# test_2.net
KiCad netlist of a schematic drawn in EAGLE
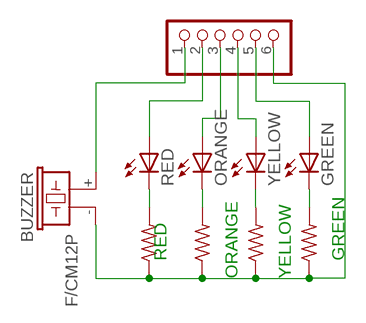
[diagram p0: schematic, sheet 1]

(export (version "E")
  (design (tool "Eeschema 10.0.6"))
  (components
    (comp (ref "BUZZER")
      (value "F/CM12P")
      (footprint "eagle-import:F_CM12P")
      (libsource (lib "eagle-import") (part "F/CM12P"))
    )
    (comp (ref "GND")
      (value "PINHD-1X6")
      (footprint "eagle-import:1X06")
      (libsource (lib "eagle-import") (part "PINHD-1X6"))
    )
    (comp (ref "GREEN")
      (value "LED5MM")
      (footprint "eagle-import:LED5MM")
      (libsource (lib "eagle-import") (part "LED5MM"))
    )
    (comp (ref "ORANGE")
      (value "LED5MM")
      (footprint "eagle-import:LED5MM")
      (libsource (lib "eagle-import") (part "LED5MM"))
    )
    (comp (ref "R1")
      (value "R-US_0204/7")
      (footprint "eagle-import:0204_7")
      (libsource (lib "eagle-import") (part "R-US_0204/7"))
    )
    (comp (ref "R2")
      (value "R-US_0204/7")
      (footprint "eagle-import:0204_7")
      (libsource (lib "eagle-import") (part "R-US_0204/7"))
    )
    (comp (ref "R3")
      (value "R-US_0204/7")
      (footprint "eagle-import:0204_7")
      (libsource (lib "eagle-import") (part "R-US_0204/7"))
    )
    (comp (ref "R4")
      (value "R-US_0204/7")
      (footprint "eagle-import:0204_7")
      (libsource (lib "eagle-import") (part "R-US_0204/7"))
    )
    (comp (ref "RED")
      (value "LED5MM")
      (footprint "eagle-import:LED5MM")
      (libsource (lib "eagle-import") (part "LED5MM"))
    )
    (comp (ref "YELLOW")
      (value "LED5MM")
      (footprint "eagle-import:LED5MM")
      (libsource (lib "eagle-import") (part "LED5MM"))
    )
  )
  (nets
    (net (code "1") (name "Net-(BUZZER-1)") (class "Default")
      (node (ref "BUZZER") (pin "+") (pinfunction "1_+") (pintype "passive"))
      (node (ref "GND") (pin "1") (pinfunction "1_1") (pintype "passive"))
    )
    (net (code "2") (name "Net-(BUZZER-2)") (class "Default")
      (node (ref "BUZZER") (pin "-") (pinfunction "2_-") (pintype "passive"))
      (node (ref "GND") (pin "6") (pinfunction "6_6") (pintype "passive"))
      (node (ref "R1") (pin "1") (pinfunction "1_1") (pintype "passive"))
      (node (ref "R2") (pin "1") (pinfunction "1_1") (pintype "passive"))
      (node (ref "R3") (pin "1") (pinfunction "1_1") (pintype "passive"))
      (node (ref "R4") (pin "1") (pinfunction "1_1") (pintype "passive"))
    )
    (net (code "3") (name "Net-(GND-Pad2)") (class "Default")
      (node (ref "GND") (pin "2") (pinfunction "2_2") (pintype "passive"))
      (node (ref "RED") (pin "A") (pinfunction "A_A") (pintype "passive"))
    )
    (net (code "4") (name "Net-(GND-Pad3)") (class "Default")
      (node (ref "GND") (pin "3") (pinfunction "3_3") (pintype "passive"))
      (node (ref "ORANGE") (pin "A") (pinfunction "A_A") (pintype "passive"))
    )
    (net (code "5") (name "Net-(GND-Pad4)") (class "Default")
      (node (ref "GND") (pin "4") (pinfunction "4_4") (pintype "passive"))
      (node (ref "YELLOW") (pin "A") (pinfunction "A_A") (pintype "passive"))
    )
    (net (code "6") (name "Net-(GND-Pad5)") (class "Default")
      (node (ref "GND") (pin "5") (pinfunction "5_5") (pintype "passive"))
      (node (ref "GREEN") (pin "A") (pinfunction "A_A") (pintype "passive"))
    )
    (net (code "7") (name "Net-(GREEN-C)") (class "Default")
      (node (ref "GREEN") (pin "K") (pinfunction "C_K") (pintype "passive"))
      (node (ref "R4") (pin "2") (pinfunction "2_2") (pintype "passive"))
    )
    (net (code "8") (name "Net-(ORANGE-C)") (class "Default")
      (node (ref "ORANGE") (pin "K") (pinfunction "C_K") (pintype "passive"))
      (node (ref "R2") (pin "2") (pinfunction "2_2") (pintype "passive"))
    )
    (net (code "9") (name "Net-(RED-C)") (class "Default")
      (node (ref "R1") (pin "2") (pinfunction "2_2") (pintype "passive"))
      (node (ref "RED") (pin "K") (pinfunction "C_K") (pintype "passive"))
    )
    (net (code "10") (name "Net-(YELLOW-C)") (class "Default")
      (node (ref "R3") (pin "2") (pinfunction "2_2") (pintype "passive"))
      (node (ref "YELLOW") (pin "K") (pinfunction "C_K") (pintype "passive"))
    )
  )
)
